# sensorboard_mag_rev0.net
KiCad netlist of a schematic drawn in EAGLE
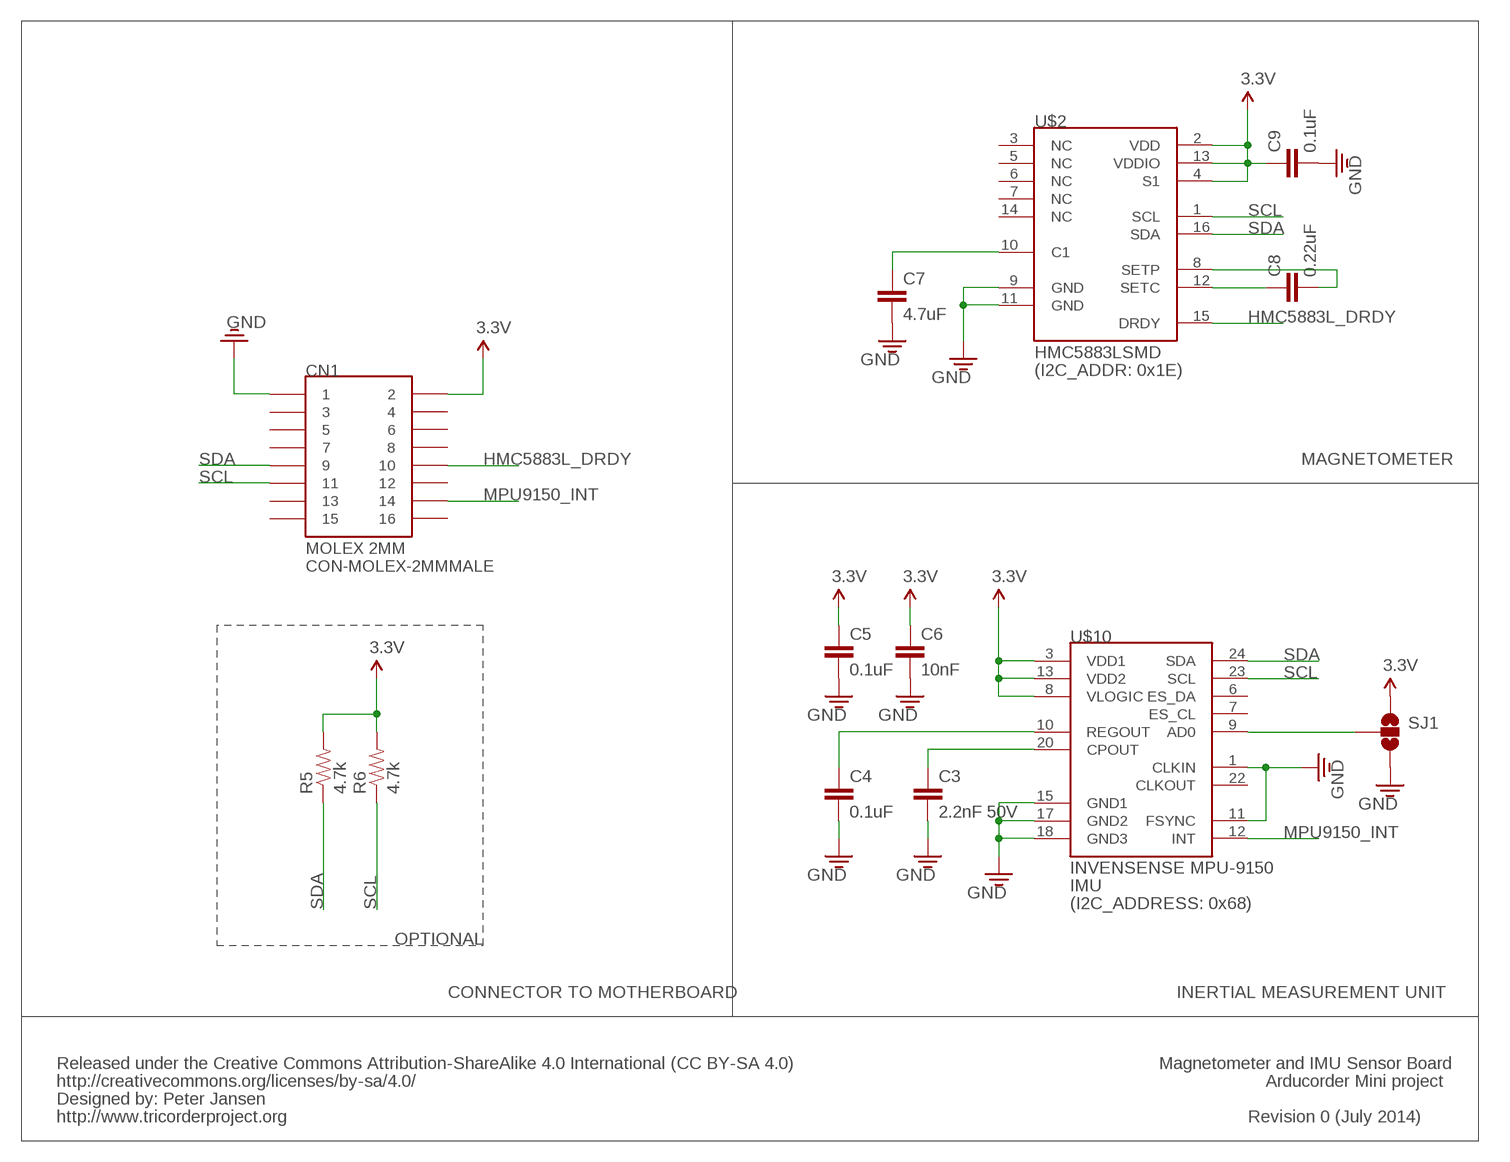
[diagram p0: schematic, sheet 1]

(export (version "E")
  (design (tool "Eeschema 10.0.6"))
  (components
    (comp (ref "C3")
      (value "2.2nF 50V")
      (footprint "eagle-import:0603")
      (libsource (lib "eagle-import") (part "CAP0603"))
    )
    (comp (ref "C4")
      (value "0.1uF")
      (footprint "eagle-import:0603")
      (libsource (lib "eagle-import") (part "CAP0603"))
    )
    (comp (ref "C5")
      (value "0.1uF")
      (footprint "eagle-import:0603")
      (libsource (lib "eagle-import") (part "CAP0603"))
    )
    (comp (ref "C6")
      (value "10nF")
      (footprint "eagle-import:0603")
      (libsource (lib "eagle-import") (part "CAP0603"))
    )
    (comp (ref "C7")
      (value "4.7uF")
      (footprint "eagle-import:0603")
      (libsource (lib "eagle-import") (part "CAP0603"))
    )
    (comp (ref "C8")
      (value "0.22uF")
      (footprint "eagle-import:0603")
      (libsource (lib "eagle-import") (part "CAP0603"))
    )
    (comp (ref "C9")
      (value "0.1uF")
      (footprint "eagle-import:0603")
      (libsource (lib "eagle-import") (part "CAP0603"))
    )
    (comp (ref "CN1")
      (value "CON-MOLEX-2MMMALE")
      (footprint "eagle-import:MOLEX-0877591650")
      (libsource (lib "eagle-import") (part "CON-MOLEX-2MMMALE"))
    )
    (comp (ref "R5")
      (value "4.7k")
      (footprint "eagle-import:0603")
      (libsource (lib "eagle-import") (part "RESISTOR0603"))
    )
    (comp (ref "R6")
      (value "4.7k")
      (footprint "eagle-import:0603")
      (libsource (lib "eagle-import") (part "RESISTOR0603"))
    )
    (comp (ref "SJ1")
      (value "SOLDERJUMPER_2WAYPASTE2&3")
      (footprint "eagle-import:SJ_3_PASTE2&3")
      (libsource (lib "eagle-import") (part "SOLDERJUMPER_2WAYPASTE2&3"))
    )
    (comp (ref "U$2")
      (value "HMC5883LSMD")
      (footprint "eagle-import:16LPCC")
      (libsource (lib "eagle-import") (part "HMC5883LSMD"))
    )
    (comp (ref "U$10")
      (value "MPU-9150")
      (footprint "eagle-import:LGA-24-(4X4MM)")
      (libsource (lib "eagle-import") (part "MPU-9150"))
    )
  )
  (nets
    (net (code "1") (name "/HMC5883L_DRDY") (class "Default")
      (node (ref "CN1") (pin "10") (pinfunction "10_10") (pintype "bidirectional"))
      (node (ref "U$2") (pin "15") (pinfunction "DRDY_15") (pintype "bidirectional"))
    )
    (net (code "2") (name "/MPU9150_INT") (class "Default")
      (node (ref "CN1") (pin "14") (pinfunction "14_14") (pintype "bidirectional"))
      (node (ref "U$10") (pin "12") (pinfunction "INT_12") (pintype "bidirectional"))
    )
    (net (code "3") (name "/SCL") (class "Default")
      (node (ref "CN1") (pin "11") (pinfunction "11_11") (pintype "bidirectional"))
      (node (ref "R6") (pin "1") (pinfunction "1_1") (pintype "passive"))
      (node (ref "U$10") (pin "23") (pinfunction "SCL_23") (pintype "bidirectional"))
      (node (ref "U$2") (pin "1") (pinfunction "SCL_1") (pintype "bidirectional"))
    )
    (net (code "4") (name "/SDA") (class "Default")
      (node (ref "CN1") (pin "9") (pinfunction "9_9") (pintype "bidirectional"))
      (node (ref "R5") (pin "1") (pinfunction "1_1") (pintype "passive"))
      (node (ref "U$10") (pin "24") (pinfunction "SDA_24") (pintype "bidirectional"))
      (node (ref "U$2") (pin "16") (pinfunction "SDA_16") (pintype "bidirectional"))
    )
    (net (code "5") (name "3.3V") (class "Default")
      (node (ref "C5") (pin "1") (pinfunction "1_1") (pintype "passive"))
      (node (ref "C6") (pin "1") (pinfunction "1_1") (pintype "passive"))
      (node (ref "C9") (pin "1") (pinfunction "1_1") (pintype "passive"))
      (node (ref "CN1") (pin "2") (pinfunction "2_2") (pintype "bidirectional"))
      (node (ref "R5") (pin "2") (pinfunction "2_2") (pintype "passive"))
      (node (ref "R6") (pin "2") (pinfunction "2_2") (pintype "passive"))
      (node (ref "SJ1") (pin "1") (pinfunction "1_1") (pintype "passive"))
      (node (ref "U$10") (pin "13") (pinfunction "VDD2_13") (pintype "bidirectional"))
      (node (ref "U$10") (pin "3") (pinfunction "VDD1_3") (pintype "bidirectional"))
      (node (ref "U$10") (pin "8") (pinfunction "VLOGIC_8") (pintype "bidirectional"))
      (node (ref "U$2") (pin "13") (pinfunction "VDDIO_13") (pintype "bidirectional"))
      (node (ref "U$2") (pin "2") (pinfunction "VDD_2") (pintype "bidirectional"))
      (node (ref "U$2") (pin "4") (pinfunction "S1_4") (pintype "bidirectional"))
    )
    (net (code "6") (name "GND") (class "Default")
      (node (ref "C3") (pin "2") (pinfunction "2_2") (pintype "passive"))
      (node (ref "C4") (pin "2") (pinfunction "2_2") (pintype "passive"))
      (node (ref "C5") (pin "2") (pinfunction "2_2") (pintype "passive"))
      (node (ref "C6") (pin "2") (pinfunction "2_2") (pintype "passive"))
      (node (ref "C7") (pin "2") (pinfunction "2_2") (pintype "passive"))
      (node (ref "C9") (pin "2") (pinfunction "2_2") (pintype "passive"))
      (node (ref "CN1") (pin "1") (pinfunction "1_1") (pintype "bidirectional"))
      (node (ref "SJ1") (pin "3") (pinfunction "3_3") (pintype "passive"))
      (node (ref "U$10") (pin "1") (pinfunction "CLKIN_1") (pintype "bidirectional"))
      (node (ref "U$10") (pin "11") (pinfunction "FSYNC_11") (pintype "bidirectional"))
      (node (ref "U$10") (pin "15") (pinfunction "GND1_15") (pintype "bidirectional"))
      (node (ref "U$10") (pin "17") (pinfunction "GND2_17") (pintype "bidirectional"))
      (node (ref "U$10") (pin "18") (pinfunction "GND3_18") (pintype "bidirectional"))
      (node (ref "U$2") (pin "11") (pinfunction "GND_11") (pintype "bidirectional"))
      (node (ref "U$2") (pin "9") (pinfunction "GND_9") (pintype "bidirectional"))
    )
    (net (code "7") (name "Net-(U$2-C1)") (class "Default")
      (node (ref "C7") (pin "1") (pinfunction "1_1") (pintype "passive"))
      (node (ref "U$2") (pin "10") (pinfunction "C1_10") (pintype "bidirectional"))
    )
    (net (code "8") (name "Net-(U$2-SETC)") (class "Default")
      (node (ref "C8") (pin "1") (pinfunction "1_1") (pintype "passive"))
      (node (ref "U$2") (pin "12") (pinfunction "SETC_12") (pintype "bidirectional"))
    )
    (net (code "9") (name "Net-(U$2-SETP)") (class "Default")
      (node (ref "C8") (pin "2") (pinfunction "2_2") (pintype "passive"))
      (node (ref "U$2") (pin "8") (pinfunction "SETP_8") (pintype "bidirectional"))
    )
    (net (code "10") (name "Net-(U$10-AD0)") (class "Default")
      (node (ref "SJ1") (pin "2") (pinfunction "2_2") (pintype "passive"))
      (node (ref "U$10") (pin "9") (pinfunction "AD0_9") (pintype "bidirectional"))
    )
    (net (code "11") (name "Net-(U$10-CPOUT)") (class "Default")
      (node (ref "C3") (pin "1") (pinfunction "1_1") (pintype "passive"))
      (node (ref "U$10") (pin "20") (pinfunction "CPOUT_20") (pintype "bidirectional"))
    )
    (net (code "12") (name "Net-(U$10-REGOUT)") (class "Default")
      (node (ref "C4") (pin "1") (pinfunction "1_1") (pintype "passive"))
      (node (ref "U$10") (pin "10") (pinfunction "REGOUT_10") (pintype "bidirectional"))
    )
    (net (code "13") (name "unconnected-(CN1-Pad3)") (class "Default")
      (node (ref "CN1") (pin "3") (pinfunction "3_3") (pintype "bidirectional"))
    )
    (net (code "14") (name "unconnected-(CN1-Pad4)") (class "Default")
      (node (ref "CN1") (pin "4") (pinfunction "4_4") (pintype "bidirectional"))
    )
    (net (code "15") (name "unconnected-(CN1-Pad5)") (class "Default")
      (node (ref "CN1") (pin "5") (pinfunction "5_5") (pintype "bidirectional"))
    )
    (net (code "16") (name "unconnected-(CN1-Pad6)") (class "Default")
      (node (ref "CN1") (pin "6") (pinfunction "6_6") (pintype "bidirectional"))
    )
    (net (code "17") (name "unconnected-(CN1-Pad7)") (class "Default")
      (node (ref "CN1") (pin "7") (pinfunction "7_7") (pintype "bidirectional"))
    )
    (net (code "18") (name "unconnected-(CN1-Pad8)") (class "Default")
      (node (ref "CN1") (pin "8") (pinfunction "8_8") (pintype "bidirectional"))
    )
    (net (code "19") (name "unconnected-(CN1-Pad12)") (class "Default")
      (node (ref "CN1") (pin "12") (pinfunction "12_12") (pintype "bidirectional"))
    )
    (net (code "20") (name "unconnected-(CN1-Pad13)") (class "Default")
      (node (ref "CN1") (pin "13") (pinfunction "13_13") (pintype "bidirectional"))
    )
    (net (code "21") (name "unconnected-(CN1-Pad15)") (class "Default")
      (node (ref "CN1") (pin "15") (pinfunction "15_15") (pintype "bidirectional"))
    )
    (net (code "22") (name "unconnected-(CN1-Pad16)") (class "Default")
      (node (ref "CN1") (pin "16") (pinfunction "16_16") (pintype "bidirectional"))
    )
    (net (code "23") (name "unconnected-(U$2-NC-Pad3)") (class "Default")
      (node (ref "U$2") (pin "3") (pinfunction "NC_3") (pintype "bidirectional"))
    )
    (net (code "24") (name "unconnected-(U$2-NC-Pad5)") (class "Default")
      (node (ref "U$2") (pin "5") (pinfunction "NC_5") (pintype "bidirectional"))
    )
    (net (code "25") (name "unconnected-(U$2-NC-Pad6)") (class "Default")
      (node (ref "U$2") (pin "6") (pinfunction "NC_6") (pintype "bidirectional"))
    )
    (net (code "26") (name "unconnected-(U$2-NC-Pad7)") (class "Default")
      (node (ref "U$2") (pin "7") (pinfunction "NC_7") (pintype "bidirectional"))
    )
    (net (code "27") (name "unconnected-(U$2-NC-Pad14)") (class "Default")
      (node (ref "U$2") (pin "14") (pinfunction "NC_14") (pintype "bidirectional"))
    )
    (net (code "28") (name "unconnected-(U$10-CLKOUT-Pad22)") (class "Default")
      (node (ref "U$10") (pin "22") (pinfunction "CLKOUT_22") (pintype "bidirectional"))
    )
    (net (code "29") (name "unconnected-(U$10-ES_CL-Pad7)") (class "Default")
      (node (ref "U$10") (pin "7") (pinfunction "ES_CL_7") (pintype "bidirectional"))
    )
    (net (code "30") (name "unconnected-(U$10-ES_DA-Pad6)") (class "Default")
      (node (ref "U$10") (pin "6") (pinfunction "ES_DA_6") (pintype "bidirectional"))
    )
  )
)
